# practice_2_1.net
KiCad netlist of a schematic drawn in EAGLE
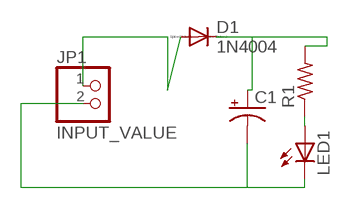
[diagram p0: schematic, sheet 1]

(export (version "E")
  (design (tool "Eeschema 10.0.6"))
  (components
    (comp (ref "C1")
      (value "CPOL-USE3.5-10")
      (footprint "eagle-import:E3,5-10")
      (libsource (lib "eagle-import") (part "CPOL-USE3.5-10"))
    )
    (comp (ref "D1")
      (value "1N4004")
      (footprint "eagle-import:DO41-10")
      (libsource (lib "eagle-import") (part "1N4004"))
    )
    (comp (ref "JP1")
      (value "INPUT_VALUE")
      (footprint "eagle-import:1X02")
      (libsource (lib "eagle-import") (part "PINHD-1X2"))
    )
    (comp (ref "LED1")
      (value "LED5MM")
      (footprint "eagle-import:LED5MM")
      (libsource (lib "eagle-import") (part "LED5MM"))
    )
    (comp (ref "R1")
      (value "R-US_0207/10")
      (footprint "eagle-import:0207_10")
      (libsource (lib "eagle-import") (part "R-US_0207/10"))
    )
  )
  (nets
    (net (code "1") (name "Net-(C1-Pad+)") (class "Default")
      (node (ref "C1") (pin "+") (pinfunction "+_+") (pintype "passive"))
      (node (ref "D1") (pin "C") (pinfunction "C_C") (pintype "passive"))
      (node (ref "R1") (pin "2") (pinfunction "2_2") (pintype "passive"))
    )
    (net (code "2") (name "Net-(D1-PadA)") (class "Default")
      (node (ref "D1") (pin "A") (pinfunction "A_A") (pintype "passive"))
      (node (ref "JP1") (pin "1") (pinfunction "1_1") (pintype "passive"))
    )
    (net (code "3") (name "Net-(LED1-C)") (class "Default")
      (node (ref "C1") (pin "-") (pinfunction "-_-") (pintype "passive"))
      (node (ref "JP1") (pin "2") (pinfunction "2_2") (pintype "passive"))
      (node (ref "LED1") (pin "K") (pinfunction "C_K") (pintype "passive"))
    )
    (net (code "4") (name "Net-(LED1-PadA)") (class "Default")
      (node (ref "LED1") (pin "A") (pinfunction "A_A") (pintype "passive"))
      (node (ref "R1") (pin "1") (pinfunction "1_1") (pintype "passive"))
    )
  )
)
